# RecoveryBoard.net
KiCad netlist of a schematic drawn in EAGLE
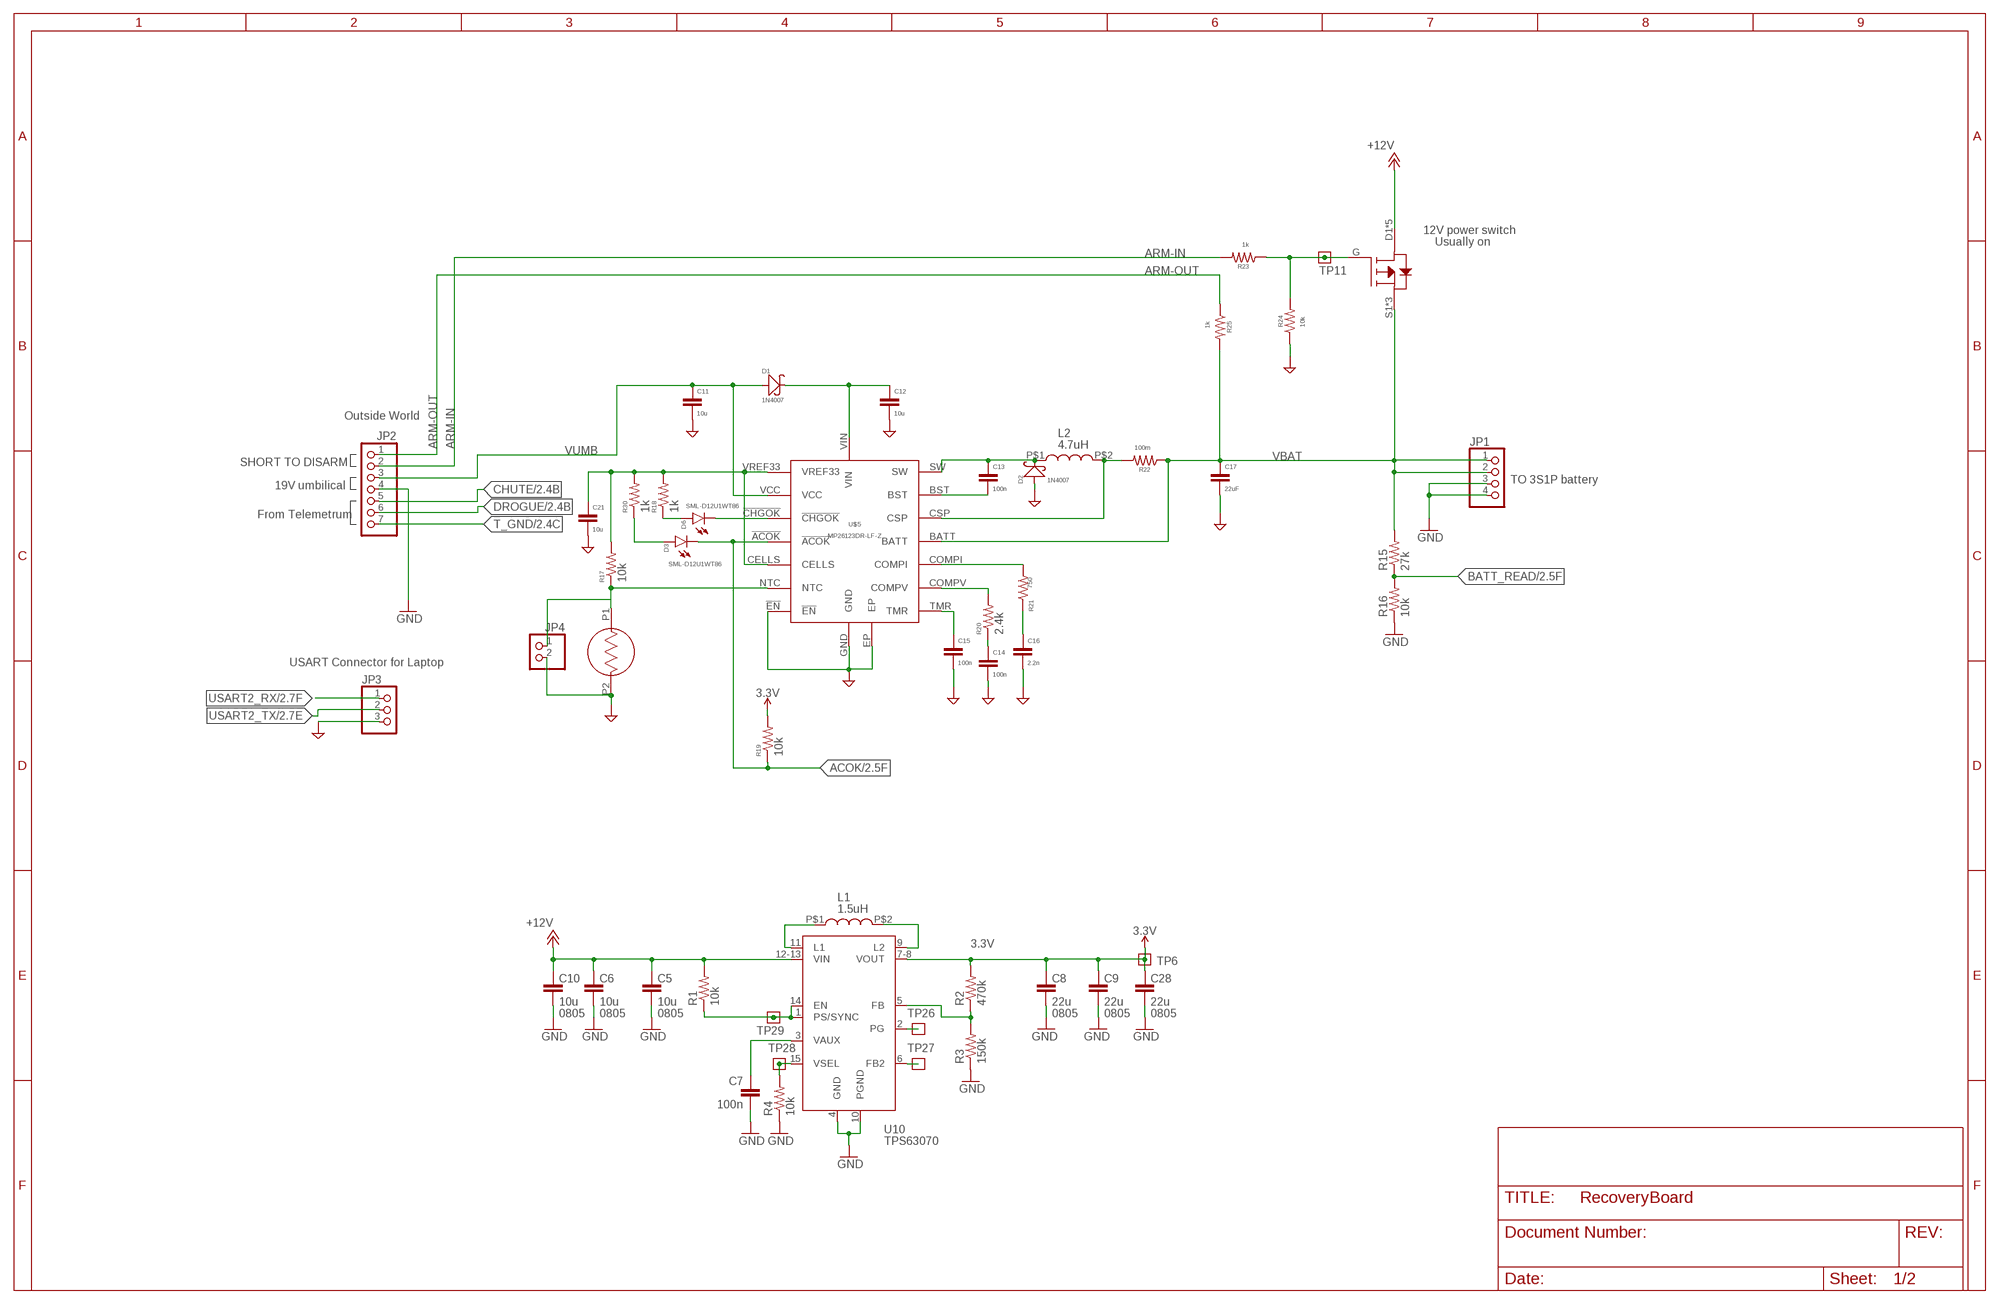
[diagram p0: schematic, sheet 1]
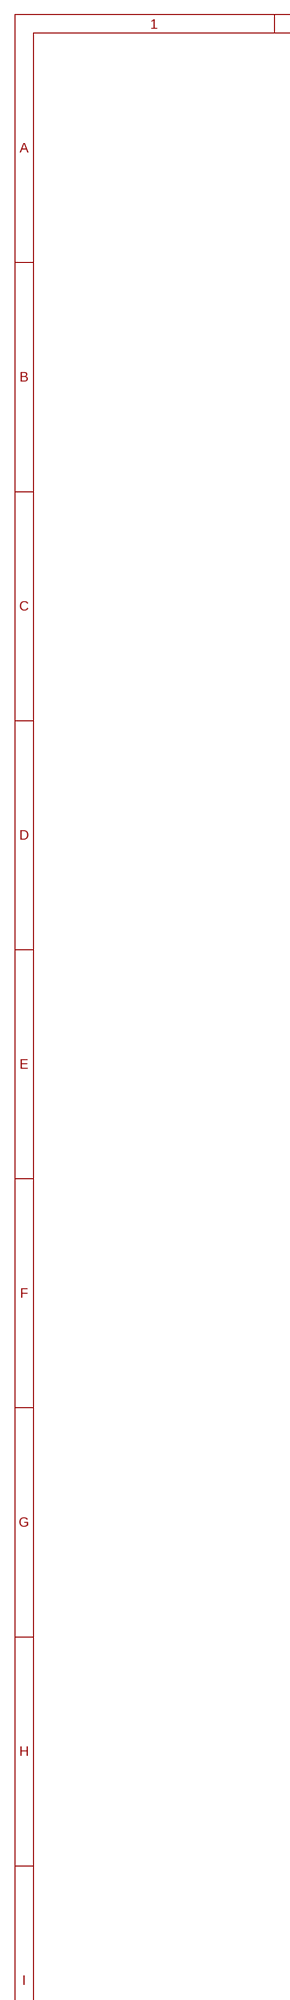
[diagram p1: schematic, sheet 2, part 1 of 2]
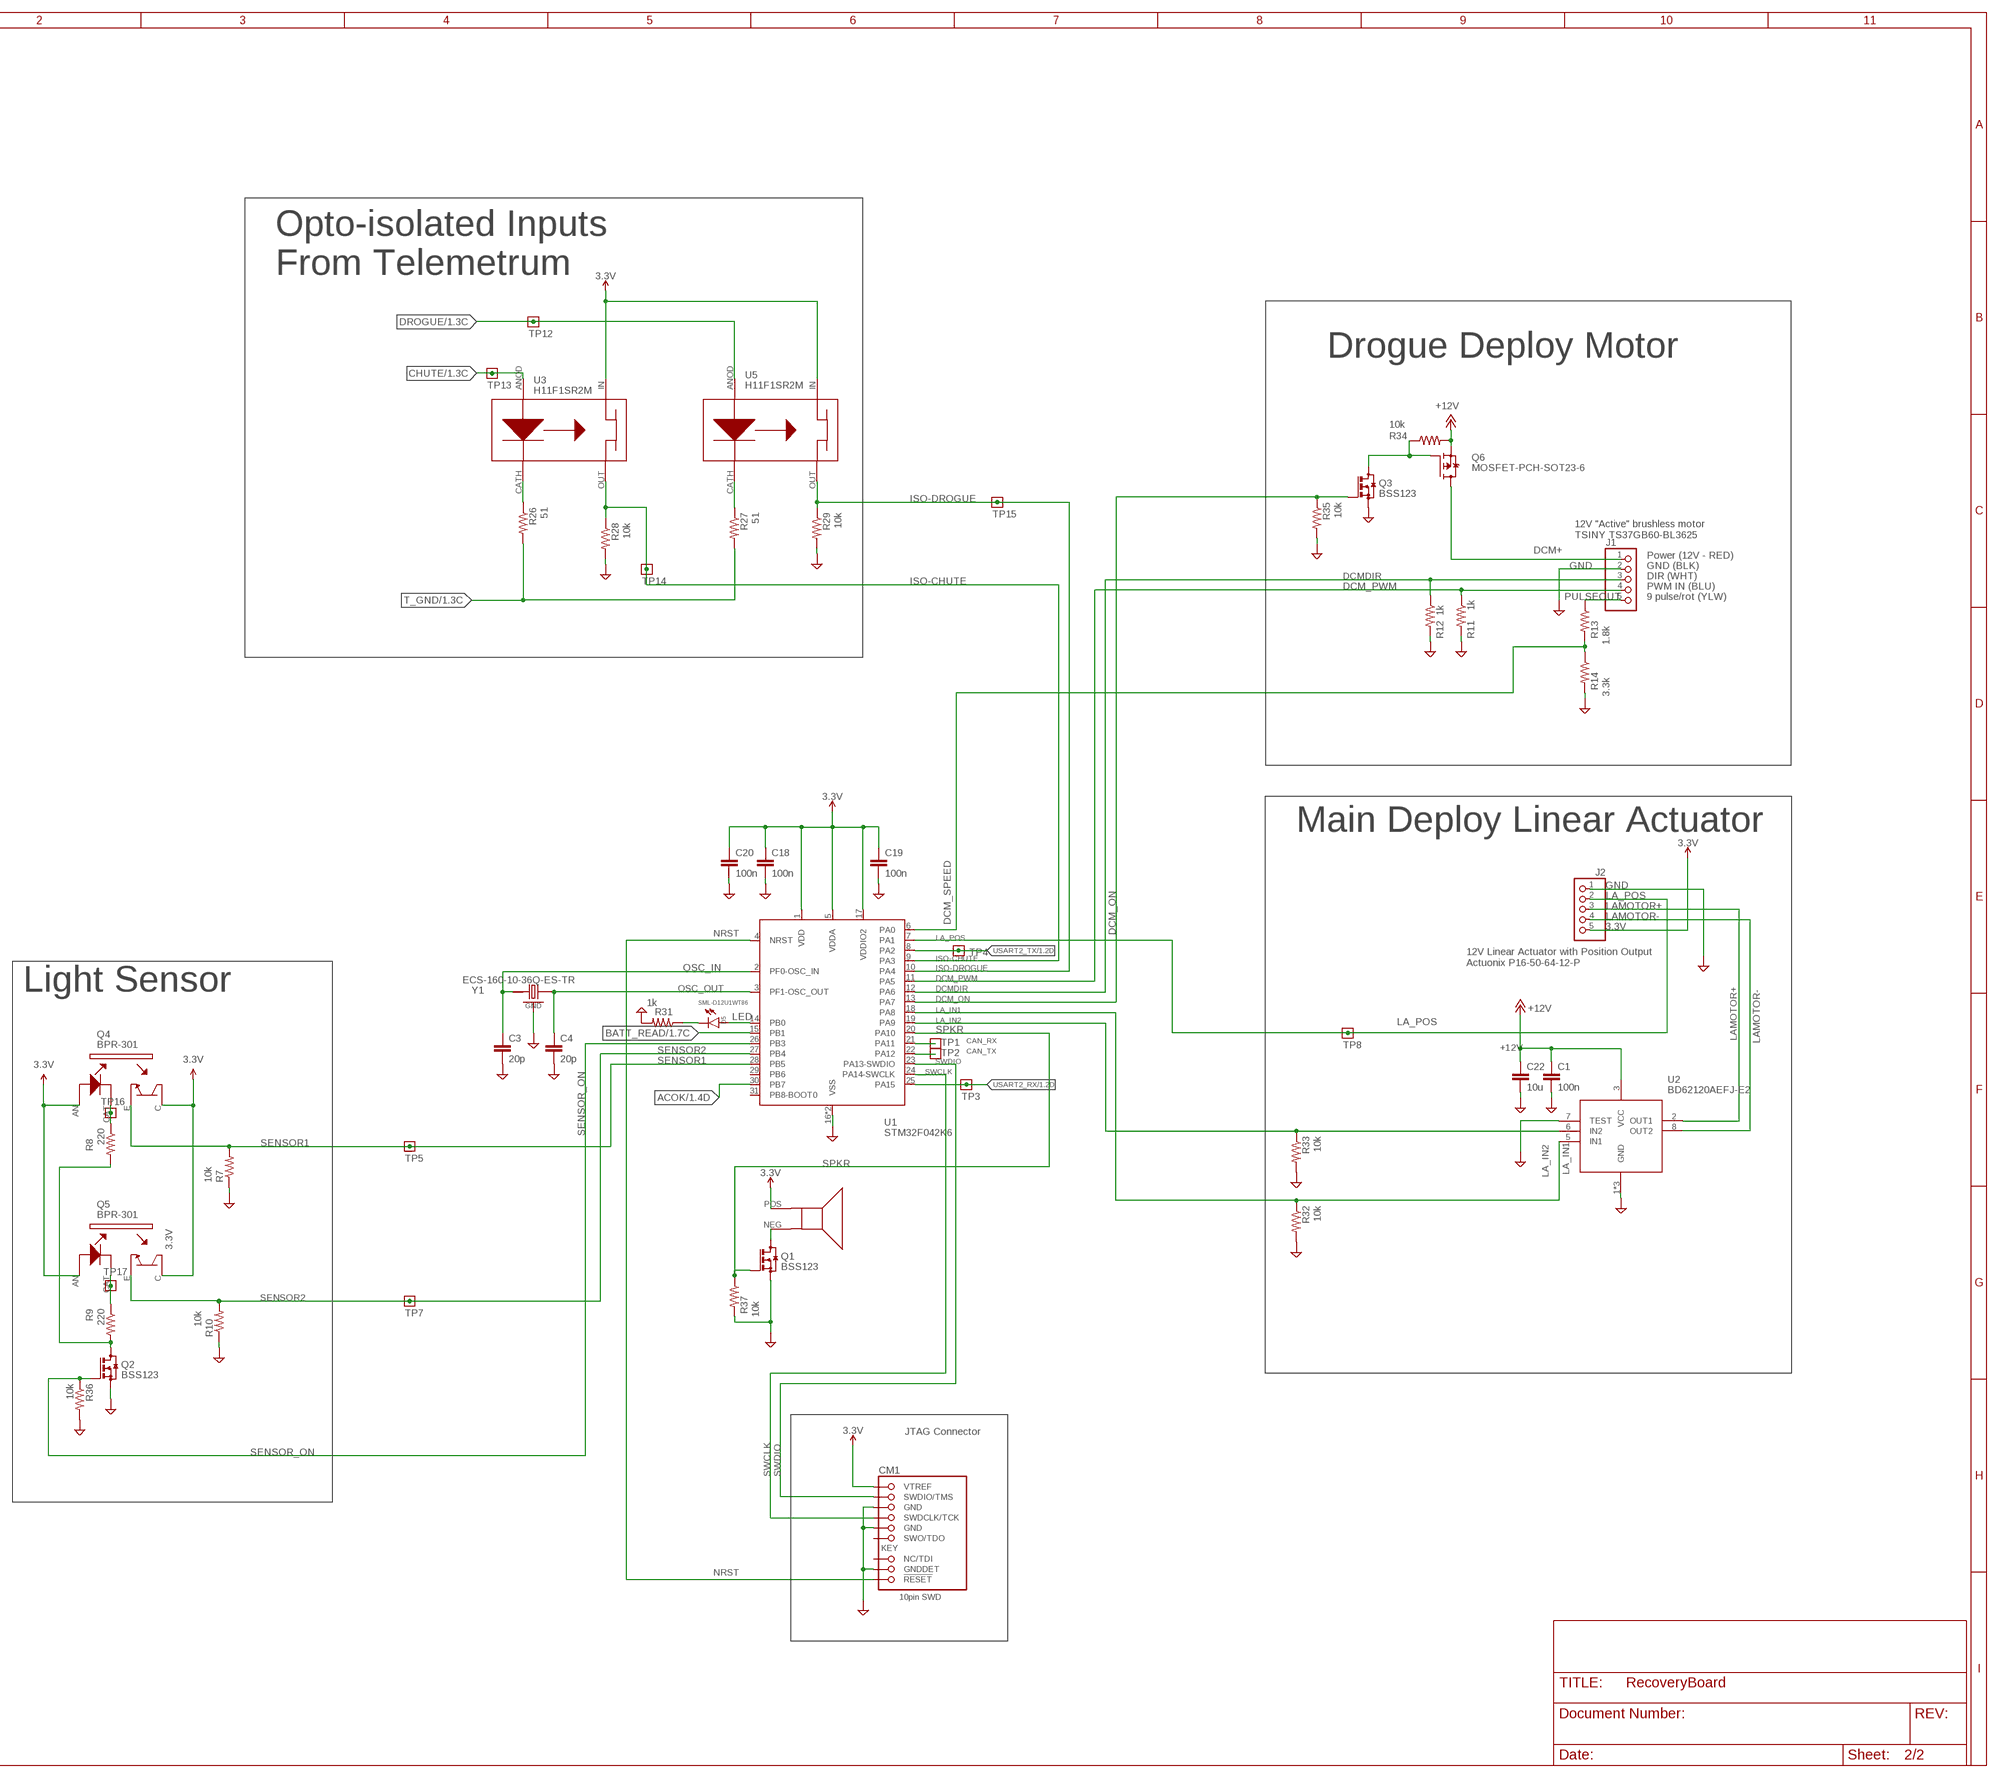
[diagram p2: schematic, sheet 2, part 2 of 2]

(export (version "E")
  (design (tool "Eeschema 10.0.6"))
  (components
    (comp (ref "C5")
      (value "10u")
      (footprint "eagle-import:.0805-C-NOSILK")
      (fields (field (name "MFR") "Samsung") (field (name "MPN") "CL05B104KO5NNNC"))
      (libsource (lib "eagle-import") (part "C-EU0805-C-NOSILK"))
    )
    (comp (ref "C6")
      (value "10u")
      (footprint "eagle-import:.0805-C-NOSILK")
      (libsource (lib "eagle-import") (part "C-EU0805-C-NOSILK"))
    )
    (comp (ref "C7")
      (value "100n")
      (footprint "eagle-import:.0603-C-NOSILK")
      (fields (field (name "MFR") "Samsung") (field (name "MPN") "CL05B104KO5NNNC"))
      (libsource (lib "eagle-import") (part "C-EU0603-C-NOSILK"))
    )
    (comp (ref "C8")
      (value "22u")
      (footprint "eagle-import:.0805-C-NOSILK")
      (fields (field (name "MFR") "Samsung") (field (name "MPN") "CL05B104KO5NNNC"))
      (libsource (lib "eagle-import") (part "C-EU0805-C-NOSILK"))
    )
    (comp (ref "C9")
      (value "22u")
      (footprint "eagle-import:.0805-C-NOSILK")
      (libsource (lib "eagle-import") (part "C-EU0805-C-NOSILK"))
    )
    (comp (ref "C10")
      (value "10u")
      (footprint "eagle-import:.0805-C-NOSILK")
      (libsource (lib "eagle-import") (part "C-EU0805-C-NOSILK"))
    )
    (comp (ref "C11")
      (value "10u")
      (footprint "eagle-import:.0805-C-NOSILK")
      (libsource (lib "eagle-import") (part "C-EU0805-C-NOSILK"))
    )
    (comp (ref "C12")
      (value "10u")
      (footprint "eagle-import:.0805-C-NOSILK")
      (libsource (lib "eagle-import") (part "C-EU0805-C-NOSILK"))
    )
    (comp (ref "C13")
      (value "100n")
      (footprint "eagle-import:.0603-C-NOSILK")
      (libsource (lib "eagle-import") (part "C-EU0603-C-NOSILK"))
    )
    (comp (ref "C14")
      (value "100n")
      (footprint "eagle-import:.0603-C-NOSILK")
      (libsource (lib "eagle-import") (part "C-EU0603-C-NOSILK"))
    )
    (comp (ref "C15")
      (value "100n")
      (footprint "eagle-import:.0603-C-NOSILK")
      (libsource (lib "eagle-import") (part "C-EU0603-C-NOSILK"))
    )
    (comp (ref "C16")
      (value "2.2n")
      (footprint "eagle-import:.0603-C-NOSILK")
      (libsource (lib "eagle-import") (part "C-EU0603-C-NOSILK"))
    )
    (comp (ref "C17")
      (value "22uF")
      (footprint "eagle-import:.0805-C-NOSILK")
      (libsource (lib "eagle-import") (part "C-EU0805-C-NOSILK"))
    )
    (comp (ref "C21")
      (value "10u")
      (footprint "eagle-import:.0805-C-NOSILK")
      (libsource (lib "eagle-import") (part "C-EU0805-C-NOSILK"))
    )
    (comp (ref "C28")
      (value "22u")
      (footprint "eagle-import:.0805-C-NOSILK")
      (libsource (lib "eagle-import") (part "C-EU0805-C-NOSILK"))
    )
    (comp (ref "D1")
      (value "1N4007")
      (footprint "eagle-import:DO-214AC")
      (libsource (lib "eagle-import") (part "DIODE-SCHOTTKY-(DO-214AC)"))
    )
    (comp (ref "D2")
      (value "1N4007")
      (footprint "eagle-import:DO-214AC")
      (libsource (lib "eagle-import") (part "DIODE-SCHOTTKY-(DO-214AC)"))
    )
    (comp (ref "D3")
      (value "SML-D12U1WT86")
      (footprint "eagle-import:CHIPLED_0603")
      (libsource (lib "eagle-import") (part "LEDCHIPLED_0603"))
    )
    (comp (ref "D6")
      (value "SML-D12U1WT86")
      (footprint "eagle-import:CHIPLED_0603")
      (libsource (lib "eagle-import") (part "LEDCHIPLED_0603"))
    )
    (comp (ref "JP1")
      (value "PINHD-1X4")
      (footprint "eagle-import:1X04")
      (libsource (lib "eagle-import") (part "PINHD-1X4"))
    )
    (comp (ref "JP2")
      (value "PINHD-1X7")
      (footprint "eagle-import:1X07")
      (libsource (lib "eagle-import") (part "PINHD-1X7"))
    )
    (comp (ref "JP3")
      (value "PINHD-1X3")
      (footprint "eagle-import:1X03")
      (libsource (lib "eagle-import") (part "PINHD-1X3"))
    )
    (comp (ref "JP4")
      (value "PINHD-1X2")
      (footprint "eagle-import:1X02")
      (libsource (lib "eagle-import") (part "PINHD-1X2"))
    )
    (comp (ref "L1")
      (value "1.5uH")
      (footprint "eagle-import:IHLP2020CZER1R5M11")
      (fields (field (name "MFR") "Vishay Dale") (field (name "MPN") "IHLP2020BZER4R7M11"))
      (libsource (lib "eagle-import") (part "IHLP2020CZER1R5M11"))
    )
    (comp (ref "L2")
      (value "4.7uH")
      (footprint "eagle-import:IHLP2020BZER4R7M11")
      (fields (field (name "MFR") "Vishay Dale") (field (name "MPN") "IHLP2020BZER4R7M11"))
      (libsource (lib "eagle-import") (part "IHLP2020BZER4R7M11"))
    )
    (comp (ref "Q7")
      (value "SI7465DP-T1-E3")
      (footprint "eagle-import:SI7465DP-T1-E3CT-ND")
      (fields (field (name "MFR") "Vishay Siliconix"))
      (libsource (lib "eagle-import") (part "SI7465DP-T1-E3"))
    )
    (comp (ref "R1")
      (value "10k")
      (footprint "eagle-import:.0603-C-NOSILK")
      (fields (field (name "MFR") "Samsung") (field (name "MPN") "RC1005F6653CS"))
      (libsource (lib "eagle-import") (part "R-US_0603-C-NOSILK"))
    )
    (comp (ref "R2")
      (value "470k")
      (footprint "eagle-import:.0603-C-NOSILK")
      (fields (field (name "MFR") "Samsung") (field (name "MPN") "RC1005F6653CS"))
      (libsource (lib "eagle-import") (part "R-US_0603-C-NOSILK"))
    )
    (comp (ref "R3")
      (value "150k")
      (footprint "eagle-import:.0603-C-NOSILK")
      (fields (field (name "MFR") "Samsung") (field (name "MPN") "RC1005F6653CS"))
      (libsource (lib "eagle-import") (part "R-US_0603-C-NOSILK"))
    )
    (comp (ref "R4")
      (value "10k")
      (footprint "eagle-import:.0603-C-NOSILK")
      (fields (field (name "MFR") "Samsung") (field (name "MPN") "RC1005F6653CS"))
      (libsource (lib "eagle-import") (part "R-US_0603-C-NOSILK"))
    )
    (comp (ref "R5")
      (value "NHQ103B375T10")
      (footprint "eagle-import:NHQ103B375T10")
      (libsource (lib "eagle-import") (part "NHQ103B375T10"))
    )
    (comp (ref "R15")
      (value "27k")
      (footprint "eagle-import:.0603-C-NOSILK")
      (fields (field (name "MFR") "Samsung") (field (name "MPN") "RC1005F6653CS"))
      (libsource (lib "eagle-import") (part "R-US_0603-C-NOSILK"))
    )
    (comp (ref "R16")
      (value "10k")
      (footprint "eagle-import:.0603-C-NOSILK")
      (fields (field (name "MFR") "Samsung") (field (name "MPN") "RC1005F6653CS"))
      (libsource (lib "eagle-import") (part "R-US_0603-C-NOSILK"))
    )
    (comp (ref "R17")
      (value "10k")
      (footprint "eagle-import:.0603-C-NOSILK")
      (libsource (lib "eagle-import") (part "R-US_0603-C-NOSILK"))
    )
    (comp (ref "R18")
      (value "1k")
      (footprint "eagle-import:.0603-C-NOSILK")
      (libsource (lib "eagle-import") (part "R-US_0603-C-NOSILK"))
    )
    (comp (ref "R19")
      (value "10k")
      (footprint "eagle-import:.0603-C-NOSILK")
      (libsource (lib "eagle-import") (part "R-US_0603-C-NOSILK"))
    )
    (comp (ref "R20")
      (value "2.4k")
      (footprint "eagle-import:.0603-C-NOSILK")
      (libsource (lib "eagle-import") (part "R-US_0603-C-NOSILK"))
    )
    (comp (ref "R21")
      (value "750")
      (footprint "eagle-import:.0603-C-NOSILK")
      (libsource (lib "eagle-import") (part "R-US_0603-C-NOSILK"))
    )
    (comp (ref "R22")
      (value "100m")
      (footprint "eagle-import:1206-C")
      (libsource (lib "eagle-import") (part "R-US_1206-C"))
    )
    (comp (ref "R23")
      (value "1k")
      (footprint "eagle-import:.0603-C-NOSILK")
      (libsource (lib "eagle-import") (part "R-US_0603-C-NOSILK"))
    )
    (comp (ref "R24")
      (value "10k")
      (footprint "eagle-import:.0603-C-NOSILK")
      (libsource (lib "eagle-import") (part "R-US_0603-C-NOSILK"))
    )
    (comp (ref "R25")
      (value "1k")
      (footprint "eagle-import:.0603-C-NOSILK")
      (libsource (lib "eagle-import") (part "R-US_0603-C-NOSILK"))
    )
    (comp (ref "R30")
      (value "1k")
      (footprint "eagle-import:.0603-C-NOSILK")
      (libsource (lib "eagle-import") (part "R-US_0603-C-NOSILK"))
    )
    (comp (ref "TP6")
      (value "TEST-POINT")
      (footprint "eagle-import:2MM-TEST-POINT")
      (libsource (lib "eagle-import") (part "TEST-POINT"))
    )
    (comp (ref "TP11")
      (value "TEST-POINT")
      (footprint "eagle-import:2MM-TEST-POINT")
      (libsource (lib "eagle-import") (part "TEST-POINT"))
    )
    (comp (ref "TP26")
      (value "TEST-POINT")
      (footprint "eagle-import:2MM-TEST-POINT")
      (libsource (lib "eagle-import") (part "TEST-POINT"))
    )
    (comp (ref "TP27")
      (value "TEST-POINT")
      (footprint "eagle-import:2MM-TEST-POINT")
      (libsource (lib "eagle-import") (part "TEST-POINT"))
    )
    (comp (ref "TP28")
      (value "TEST-POINT")
      (footprint "eagle-import:2MM-TEST-POINT")
      (libsource (lib "eagle-import") (part "TEST-POINT"))
    )
    (comp (ref "TP29")
      (value "TEST-POINT")
      (footprint "eagle-import:2MM-TEST-POINT")
      (libsource (lib "eagle-import") (part "TEST-POINT"))
    )
    (comp (ref "U$5")
      (value "MP26123DR-LF-Z")
      (footprint "eagle-import:MP26123DR-LF-Z")
      (libsource (lib "eagle-import") (part "MP26123DR-LF-Z"))
    )
    (comp (ref "U10")
      (value "TPS63070")
      (footprint "eagle-import:TPS63070X")
      (libsource (lib "eagle-import") (part "TPS63070X"))
    )
    (comp (ref "C1")
      (value "100n")
      (footprint "eagle-import:.0603-C-NOSILK")
      (libsource (lib "eagle-import") (part "C-EU0603-C-NOSILK"))
    )
    (comp (ref "C3")
      (value "20p")
      (footprint "eagle-import:.0603-C-NOSILK")
      (libsource (lib "eagle-import") (part "C-EU0603-C-NOSILK"))
    )
    (comp (ref "C4")
      (value "20p")
      (footprint "eagle-import:.0603-C-NOSILK")
      (libsource (lib "eagle-import") (part "C-EU0603-C-NOSILK"))
    )
    (comp (ref "C18")
      (value "100n")
      (footprint "eagle-import:.0603-C-NOSILK")
      (libsource (lib "eagle-import") (part "C-EU0603-C-NOSILK"))
    )
    (comp (ref "C19")
      (value "100n")
      (footprint "eagle-import:.0603-C-NOSILK")
      (libsource (lib "eagle-import") (part "C-EU0603-C-NOSILK"))
    )
    (comp (ref "C20")
      (value "100n")
      (footprint "eagle-import:.0603-C-NOSILK")
      (libsource (lib "eagle-import") (part "C-EU0603-C-NOSILK"))
    )
    (comp (ref "C22")
      (value "10u")
      (footprint "eagle-import:.0805-A-NOSILK")
      (libsource (lib "eagle-import") (part "C-EU0805-A-NOSILK"))
    )
    (comp (ref "CM1")
      (value "FTSH-105-XX-X-DV-K")
      (footprint "eagle-import:CON10_2X5_DUK_FTSH")
      (libsource (lib "eagle-import") (part "FTSH-105-XX-X-DV-K"))
    )
    (comp (ref "D5")
      (value "SML-D12U1WT86")
      (footprint "eagle-import:CHIPLED_0603")
      (libsource (lib "eagle-import") (part "LEDCHIPLED_0603"))
    )
    (comp (ref "J1")
      (value "PINHD-1X5")
      (footprint "eagle-import:1X05")
      (libsource (lib "eagle-import") (part "PINHD-1X5"))
    )
    (comp (ref "J2")
      (value "PINHD-1X5")
      (footprint "eagle-import:1X05")
      (libsource (lib "eagle-import") (part "PINHD-1X5"))
    )
    (comp (ref "Q1")
      (value "BSS123")
      (footprint "eagle-import:SOT23")
      (libsource (lib "eagle-import") (part "BSS123"))
    )
    (comp (ref "Q2")
      (value "BSS123")
      (footprint "eagle-import:SOT23")
      (libsource (lib "eagle-import") (part "BSS123"))
    )
    (comp (ref "Q3")
      (value "BSS123")
      (footprint "eagle-import:SOT23")
      (libsource (lib "eagle-import") (part "BSS123"))
    )
    (comp (ref "Q4")
      (value "BPR-301")
      (footprint "eagle-import:BPR-301")
      (libsource (lib "eagle-import") (part "BPR-301"))
    )
    (comp (ref "Q5")
      (value "BPR-301")
      (footprint "eagle-import:BPR-301")
      (libsource (lib "eagle-import") (part "BPR-301"))
    )
    (comp (ref "Q6")
      (value "MOSFET-PCH-SOT23-6")
      (footprint "eagle-import:SOT23-6")
      (libsource (lib "eagle-import") (part "MOSFET-PCH-SOT23-6"))
    )
    (comp (ref "R7")
      (value "10k")
      (footprint "eagle-import:.0603-C-NOSILK")
      (libsource (lib "eagle-import") (part "R-US_0603-C-NOSILK"))
    )
    (comp (ref "R8")
      (value "220")
      (footprint "eagle-import:.0603-C-NOSILK")
      (libsource (lib "eagle-import") (part "R-US_0603-C-NOSILK"))
    )
    (comp (ref "R9")
      (value "220")
      (footprint "eagle-import:.0603-C-NOSILK")
      (libsource (lib "eagle-import") (part "R-US_0603-C-NOSILK"))
    )
    (comp (ref "R10")
      (value "10k")
      (footprint "eagle-import:.0603-C-NOSILK")
      (libsource (lib "eagle-import") (part "R-US_0603-C-NOSILK"))
    )
    (comp (ref "R11")
      (value "1k")
      (footprint "eagle-import:.0603-C-NOSILK")
      (libsource (lib "eagle-import") (part "R-US_0603-C-NOSILK"))
    )
    (comp (ref "R12")
      (value "1k")
      (footprint "eagle-import:.0603-C-NOSILK")
      (libsource (lib "eagle-import") (part "R-US_0603-C-NOSILK"))
    )
    (comp (ref "R13")
      (value "1.8k")
      (footprint "eagle-import:.0603-C-NOSILK")
      (libsource (lib "eagle-import") (part "R-US_0603-C-NOSILK"))
    )
    (comp (ref "R14")
      (value "3.3k")
      (footprint "eagle-import:.0603-C-NOSILK")
      (libsource (lib "eagle-import") (part "R-US_0603-C-NOSILK"))
    )
    (comp (ref "R26")
      (value "51")
      (footprint "eagle-import:.0603-C-NOSILK")
      (libsource (lib "eagle-import") (part "R-US_0603-C-NOSILK"))
    )
    (comp (ref "R27")
      (value "51")
      (footprint "eagle-import:.0603-C-NOSILK")
      (libsource (lib "eagle-import") (part "R-US_0603-C-NOSILK"))
    )
    (comp (ref "R28")
      (value "10k")
      (footprint "eagle-import:.0603-C-NOSILK")
      (libsource (lib "eagle-import") (part "R-US_0603-C-NOSILK"))
    )
    (comp (ref "R29")
      (value "10k")
      (footprint "eagle-import:.0603-C-NOSILK")
      (libsource (lib "eagle-import") (part "R-US_0603-C-NOSILK"))
    )
    (comp (ref "R31")
      (value "1k")
      (footprint "eagle-import:.0603-C-NOSILK")
      (libsource (lib "eagle-import") (part "R-US_0603-C-NOSILK"))
    )
    (comp (ref "R32")
      (value "10k")
      (footprint "eagle-import:.0603-C-NOSILK")
      (libsource (lib "eagle-import") (part "R-US_0603-C-NOSILK"))
    )
    (comp (ref "R33")
      (value "10k")
      (footprint "eagle-import:.0603-C-NOSILK")
      (libsource (lib "eagle-import") (part "R-US_0603-C-NOSILK"))
    )
    (comp (ref "R34")
      (value "10k")
      (footprint "eagle-import:.0603-C-NOSILK")
      (libsource (lib "eagle-import") (part "R-US_0603-C-NOSILK"))
    )
    (comp (ref "R35")
      (value "10k")
      (footprint "eagle-import:.0603-C-NOSILK")
      (libsource (lib "eagle-import") (part "R-US_0603-C-NOSILK"))
    )
    (comp (ref "R36")
      (value "10k")
      (footprint "eagle-import:.0603-C-NOSILK")
      (libsource (lib "eagle-import") (part "R-US_0603-C-NOSILK"))
    )
    (comp (ref "R37")
      (value "10k")
      (footprint "eagle-import:.0603-C-NOSILK")
      (libsource (lib "eagle-import") (part "R-US_0603-C-NOSILK"))
    )
    (comp (ref "TP1")
      (value "TEST-POINT")
      (footprint "eagle-import:2MM-TEST-POINT")
      (libsource (lib "eagle-import") (part "TEST-POINT"))
    )
    (comp (ref "TP2")
      (value "TEST-POINT")
      (footprint "eagle-import:2MM-TEST-POINT")
      (libsource (lib "eagle-import") (part "TEST-POINT"))
    )
    (comp (ref "TP3")
      (value "TEST-POINT")
      (footprint "eagle-import:2MM-TEST-POINT")
      (libsource (lib "eagle-import") (part "TEST-POINT"))
    )
    (comp (ref "TP4")
      (value "TEST-POINT")
      (footprint "eagle-import:2MM-TEST-POINT")
      (libsource (lib "eagle-import") (part "TEST-POINT"))
    )
    (comp (ref "TP5")
      (value "TEST-POINT")
      (footprint "eagle-import:2MM-TEST-POINT")
      (libsource (lib "eagle-import") (part "TEST-POINT"))
    )
    (comp (ref "TP7")
      (value "TEST-POINT")
      (footprint "eagle-import:2MM-TEST-POINT")
      (libsource (lib "eagle-import") (part "TEST-POINT"))
    )
    (comp (ref "TP8")
      (value "TEST-POINT")
      (footprint "eagle-import:2MM-TEST-POINT")
      (libsource (lib "eagle-import") (part "TEST-POINT"))
    )
    (comp (ref "TP12")
      (value "TEST-POINT")
      (footprint "eagle-import:2MM-TEST-POINT")
      (libsource (lib "eagle-import") (part "TEST-POINT"))
    )
    (comp (ref "TP13")
      (value "TEST-POINT")
      (footprint "eagle-import:2MM-TEST-POINT")
      (libsource (lib "eagle-import") (part "TEST-POINT"))
    )
    (comp (ref "TP14")
      (value "TEST-POINT")
      (footprint "eagle-import:2MM-TEST-POINT")
      (libsource (lib "eagle-import") (part "TEST-POINT"))
    )
    (comp (ref "TP15")
      (value "TEST-POINT")
      (footprint "eagle-import:2MM-TEST-POINT")
      (libsource (lib "eagle-import") (part "TEST-POINT"))
    )
    (comp (ref "TP16")
      (value "TEST-POINT")
      (footprint "eagle-import:2MM-TEST-POINT")
      (libsource (lib "eagle-import") (part "TEST-POINT"))
    )
    (comp (ref "TP17")
      (value "TEST-POINT")
      (footprint "eagle-import:2MM-TEST-POINT")
      (libsource (lib "eagle-import") (part "TEST-POINT"))
    )
    (comp (ref "U$7")
      (value "SMT-0440-S-R")
      (footprint "eagle-import:SMT-0440-S-R")
      (libsource (lib "eagle-import") (part "SMT-0440-S-R"))
    )
    (comp (ref "U1")
      (value "STM32F042K6")
      (footprint "eagle-import:QFP32-7X7")
      (libsource (lib "eagle-import") (part "STM32F042K6"))
    )
    (comp (ref "U2")
      (value "BD62120AEFJ-E2")
      (footprint "eagle-import:SOIC127P600X100-9N")
      (fields (field (name "MOUSER_PART_NUMBER") "755-BD62120AEFJ-E2"))
      (libsource (lib "eagle-import") (part "BD62120AEFJ-E2"))
    )
    (comp (ref "U3")
      (value "H11F1SR2M")
      (footprint "eagle-import:H11F1SR2M")
      (libsource (lib "eagle-import") (part "H11F1SR2M"))
    )
    (comp (ref "U5")
      (value "H11F1SR2M")
      (footprint "eagle-import:H11F1SR2M")
      (libsource (lib "eagle-import") (part "H11F1SR2M"))
    )
    (comp (ref "Y1")
      (value "ECS-160-10-36Q-ES-TR")
      (footprint "eagle-import:XTAL_ECS-160-10-36Q-ES-TR")
      (fields (field (name "DIGI-KEY_PART_NUMBER") "XC2181CT-ND") (field (name "MF") "ECS Inc."))
      (libsource (lib "eagle-import") (part "ECS-160-10-36Q-ES-TR"))
    )
  )
  (nets
    (net (code "1") (name "+12V") (class "Default")
      (node (ref "C1") (pin "1") (pinfunction "1_1") (pintype "passive"))
      (node (ref "C10") (pin "1") (pinfunction "1_1") (pintype "passive"))
      (node (ref "C22") (pin "1") (pinfunction "1_1") (pintype "passive"))
      (node (ref "C5") (pin "1") (pinfunction "1_1") (pintype "passive"))
      (node (ref "C6") (pin "1") (pinfunction "1_1") (pintype "passive"))
      (node (ref "Q6") (pin "4") (pinfunction "S_4") (pintype "passive"))
      (node (ref "Q7") (pin "D1") (pinfunction "D_D1") (pintype "bidirectional"))
      (node (ref "Q7") (pin "D2") (pinfunction "D_D2") (pintype "bidirectional"))
      (node (ref "Q7") (pin "D3") (pinfunction "D_D3") (pintype "bidirectional"))
      (node (ref "Q7") (pin "D4") (pinfunction "D_D4") (pintype "bidirectional"))
      (node (ref "Q7") (pin "DPAD") (pinfunction "D_DPAD") (pintype "bidirectional"))
      (node (ref "R1") (pin "2") (pinfunction "2_2") (pintype "passive"))
      (node (ref "R34") (pin "2") (pinfunction "2_2") (pintype "passive"))
      (node (ref "U10") (pin "12-13") (pinfunction "VIN_12-13") (pintype "power_in"))
      (node (ref "U2") (pin "3") (pinfunction "VCC_3") (pintype "bidirectional"))
    )
    (net (code "2") (name "3.3V") (class "Default")
      (node (ref "C18") (pin "1") (pinfunction "1_1") (pintype "passive"))
      (node (ref "C19") (pin "1") (pinfunction "1_1") (pintype "passive"))
      (node (ref "C20") (pin "1") (pinfunction "1_1") (pintype "passive"))
      (node (ref "C28") (pin "1") (pinfunction "1_1") (pintype "passive"))
      (node (ref "C8") (pin "1") (pinfunction "1_1") (pintype "passive"))
      (node (ref "C9") (pin "1") (pinfunction "1_1") (pintype "passive"))
      (node (ref "CM1") (pin "1") (pinfunction "VTREF_1") (pintype "passive"))
      (node (ref "J2") (pin "5") (pinfunction "5_5") (pintype "passive"))
      (node (ref "Q4") (pin "AN") (pinfunction "ANOD_AN") (pintype "bidirectional"))
      (node (ref "Q4") (pin "C") (pinfunction "COLL_C") (pintype "bidirectional"))
      (node (ref "Q5") (pin "AN") (pinfunction "ANOD_AN") (pintype "bidirectional"))
      (node (ref "Q5") (pin "C") (pinfunction "COLL_C") (pintype "bidirectional"))
      (node (ref "R19") (pin "2") (pinfunction "2_2") (pintype "passive"))
      (node (ref "R2") (pin "2") (pinfunction "2_2") (pintype "passive"))
      (node (ref "TP6") (pin "1") (pinfunction "1_1") (pintype "passive"))
      (node (ref "U$7") (pin "POS") (pinfunction "POS_POS") (pintype "bidirectional"))
      (node (ref "U1") (pin "1") (pinfunction "VDD_1") (pintype "power_in"))
      (node (ref "U1") (pin "17") (pinfunction "VDDIO2_17") (pintype "power_in"))
      (node (ref "U1") (pin "5") (pinfunction "VDDA_5") (pintype "power_in"))
      (node (ref "U10") (pin "7-8") (pinfunction "VOUT_7-8") (pintype "power_in"))
      (node (ref "U3") (pin "IN") (pinfunction "IN_IN") (pintype "bidirectional"))
      (node (ref "U5") (pin "IN") (pinfunction "IN_IN") (pintype "bidirectional"))
    )
    (net (code "3") (name "ACOK") (class "Default")
      (node (ref "D3") (pin "C") (pinfunction "C_C") (pintype "passive"))
      (node (ref "R19") (pin "1") (pinfunction "1_1") (pintype "passive"))
      (node (ref "U$5") (pin "!ACOK") (pinfunction "~{ACOK}_!ACOK") (pintype "bidirectional"))
      (node (ref "U1") (pin "30") (pinfunction "PB7_30") (pintype "bidirectional"))
    )
    (net (code "4") (name "ARM-IN") (class "Default")
      (node (ref "JP2") (pin "2") (pinfunction "2_2") (pintype "passive"))
      (node (ref "R23") (pin "2") (pinfunction "2_2") (pintype "passive"))
    )
    (net (code "5") (name "ARM-OUT") (class "Default")
      (node (ref "JP2") (pin "1") (pinfunction "1_1") (pintype "passive"))
      (node (ref "R25") (pin "1") (pinfunction "1_1") (pintype "passive"))
    )
    (net (code "6") (name "BATT_READ") (class "Default")
      (node (ref "R15") (pin "1") (pinfunction "1_1") (pintype "passive"))
      (node (ref "R16") (pin "2") (pinfunction "2_2") (pintype "passive"))
      (node (ref "U1") (pin "15") (pinfunction "PB1_15") (pintype "bidirectional"))
    )
    (net (code "7") (name "CAN_RX") (class "Default")
      (node (ref "TP1") (pin "1") (pinfunction "1_1") (pintype "passive"))
      (node (ref "U1") (pin "21") (pinfunction "PA11_21") (pintype "bidirectional"))
    )
    (net (code "8") (name "CAN_TX") (class "Default")
      (node (ref "TP2") (pin "1") (pinfunction "1_1") (pintype "passive"))
      (node (ref "U1") (pin "22") (pinfunction "PA12_22") (pintype "bidirectional"))
    )
    (net (code "9") (name "CHUTE") (class "Default")
      (node (ref "JP2") (pin "5") (pinfunction "5_5") (pintype "passive"))
      (node (ref "TP13") (pin "1") (pinfunction "1_1") (pintype "passive"))
      (node (ref "U3") (pin "ANOD") (pinfunction "ANOD_ANOD") (pintype "bidirectional"))
    )
    (net (code "10") (name "DCM+") (class "Default")
      (node (ref "J1") (pin "1") (pinfunction "1_1") (pintype "passive"))
      (node (ref "Q6") (pin "1") (pinfunction "D_1") (pintype "passive"))
      (node (ref "Q6") (pin "2") (pinfunction "D_2") (pintype "passive"))
      (node (ref "Q6") (pin "5") (pinfunction "D_5") (pintype "passive"))
      (node (ref "Q6") (pin "6") (pinfunction "D_6") (pintype "passive"))
    )
    (net (code "11") (name "DCMDIR") (class "Default")
      (node (ref "J1") (pin "3") (pinfunction "3_3") (pintype "passive"))
      (node (ref "R12") (pin "1") (pinfunction "1_1") (pintype "passive"))
      (node (ref "U1") (pin "12") (pinfunction "PA6_12") (pintype "bidirectional"))
    )
    (net (code "12") (name "DCM_ON") (class "Default")
      (node (ref "Q3") (pin "1") (pinfunction "G_1") (pintype "passive"))
      (node (ref "R35") (pin "1") (pinfunction "1_1") (pintype "passive"))
      (node (ref "U1") (pin "13") (pinfunction "PA7_13") (pintype "bidirectional"))
    )
    (net (code "13") (name "DCM_PWM") (class "Default")
      (node (ref "J1") (pin "4") (pinfunction "4_4") (pintype "passive"))
      (node (ref "R11") (pin "1") (pinfunction "1_1") (pintype "passive"))
      (node (ref "U1") (pin "11") (pinfunction "PA5_11") (pintype "bidirectional"))
    )
    (net (code "14") (name "DCM_SPEED") (class "Default")
      (node (ref "R13") (pin "2") (pinfunction "2_2") (pintype "passive"))
      (node (ref "R14") (pin "1") (pinfunction "1_1") (pintype "passive"))
      (node (ref "U1") (pin "6") (pinfunction "PA0_6") (pintype "bidirectional"))
    )
    (net (code "15") (name "DROGUE") (class "Default")
      (node (ref "JP2") (pin "6") (pinfunction "6_6") (pintype "passive"))
      (node (ref "TP12") (pin "1") (pinfunction "1_1") (pintype "passive"))
      (node (ref "U5") (pin "ANOD") (pinfunction "ANOD_ANOD") (pintype "bidirectional"))
    )
    (net (code "16") (name "GND") (class "Default")
      (node (ref "C1") (pin "2") (pinfunction "2_2") (pintype "passive"))
      (node (ref "C10") (pin "2") (pinfunction "2_2") (pintype "passive"))
      (node (ref "C11") (pin "2") (pinfunction "2_2") (pintype "passive"))
      (node (ref "C12") (pin "2") (pinfunction "2_2") (pintype "passive"))
      (node (ref "C14") (pin "2") (pinfunction "2_2") (pintype "passive"))
      (node (ref "C15") (pin "2") (pinfunction "2_2") (pintype "passive"))
      (node (ref "C16") (pin "2") (pinfunction "2_2") (pintype "passive"))
      (node (ref "C17") (pin "2") (pinfunction "2_2") (pintype "passive"))
      (node (ref "C18") (pin "2") (pinfunction "2_2") (pintype "passive"))
      (node (ref "C19") (pin "2") (pinfunction "2_2") (pintype "passive"))
      (node (ref "C20") (pin "2") (pinfunction "2_2") (pintype "passive"))
      (node (ref "C21") (pin "2") (pinfunction "2_2") (pintype "passive"))
      (node (ref "C22") (pin "2") (pinfunction "2_2") (pintype "passive"))
      (node (ref "C28") (pin "2") (pinfunction "2_2") (pintype "passive"))
      (node (ref "C3") (pin "2") (pinfunction "2_2") (pintype "passive"))
      (node (ref "C4") (pin "2") (pinfunction "2_2") (pintype "passive"))
      (node (ref "C5") (pin "2") (pinfunction "2_2") (pintype "passive"))
      (node (ref "C6") (pin "2") (pinfunction "2_2") (pintype "passive"))
      (node (ref "C7") (pin "2") (pinfunction "2_2") (pintype "passive"))
      (node (ref "C8") (pin "2") (pinfunction "2_2") (pintype "passive"))
      (node (ref "C9") (pin "2") (pinfunction "2_2") (pintype "passive"))
      (node (ref "CM1") (pin "3") (pinfunction "GND_3") (pintype "passive"))
      (node (ref "CM1") (pin "5") (pinfunction "GND_5") (pintype "passive"))
      (node (ref "CM1") (pin "9") (pinfunction "GNDDET_9") (pintype "passive"))
      (node (ref "D2") (pin "1") (pinfunction "+_1") (pintype "passive"))
      (node (ref "J1") (pin "2") (pinfunction "2_2") (pintype "passive"))
      (node (ref "J2") (pin "1") (pinfunction "1_1") (pintype "passive"))
      (node (ref "JP1") (pin "3") (pinfunction "3_3") (pintype "passive"))
      (node (ref "JP1") (pin "4") (pinfunction "4_4") (pintype "passive"))
      (node (ref "JP2") (pin "4") (pinfunction "4_4") (pintype "passive"))
      (node (ref "JP3") (pin "3") (pinfunction "3_3") (pintype "passive"))
      (node (ref "JP4") (pin "2") (pinfunction "2_2") (pintype "passive"))
      (node (ref "Q1") (pin "2") (pinfunction "S_2") (pintype "passive"))
      (node (ref "Q2") (pin "2") (pinfunction "S_2") (pintype "passive"))
      (node (ref "Q3") (pin "2") (pinfunction "S_2") (pintype "passive"))
      (node (ref "R10") (pin "1") (pinfunction "1_1") (pintype "passive"))
      (node (ref "R11") (pin "2") (pinfunction "2_2") (pintype "passive"))
      (node (ref "R12") (pin "2") (pinfunction "2_2") (pintype "passive"))
      (node (ref "R14") (pin "2") (pinfunction "2_2") (pintype "passive"))
      (node (ref "R16") (pin "1") (pinfunction "1_1") (pintype "passive"))
      (node (ref "R24") (pin "1") (pinfunction "1_1") (pintype "passive"))
      (node (ref "R28") (pin "2") (pinfunction "2_2") (pintype "passive"))
      (node (ref "R29") (pin "2") (pinfunction "2_2") (pintype "passive"))
      (node (ref "R3") (pin "1") (pinfunction "1_1") (pintype "passive"))
      (node (ref "R31") (pin "2") (pinfunction "2_2") (pintype "passive"))
      (node (ref "R32") (pin "2") (pinfunction "2_2") (pintype "passive"))
      (node (ref "R33") (pin "2") (pinfunction "2_2") (pintype "passive"))
      (node (ref "R35") (pin "2") (pinfunction "2_2") (pintype "passive"))
      (node (ref "R36") (pin "2") (pinfunction "2_2") (pintype "passive"))
      (node (ref "R37") (pin "2") (pinfunction "2_2") (pintype "passive"))
      (node (ref "R4") (pin "1") (pinfunction "1_1") (pintype "passive"))
      (node (ref "R5") (pin "P2") (pinfunction "P$2_P2") (pintype "bidirectional"))
      (node (ref "R7") (pin "1") (pinfunction "1_1") (pintype "passive"))
      (node (ref "U$5") (pin "!EN") (pinfunction "~{EN}_!EN") (pintype "bidirectional"))
      (node (ref "U$5") (pin "EP") (pinfunction "EP_EP") (pintype "bidirectional"))
      (node (ref "U$5") (pin "GND") (pinfunction "GND_GND") (pintype "bidirectional"))
      (node (ref "U1") (pin "16") (pinfunction "VSS_16") (pintype "power_in"))
      (node (ref "U1") (pin "32") (pinfunction "VSS_32") (pintype "power_in"))
      (node (ref "U10") (pin "10") (pinfunction "PGND_10") (pintype "power_in"))
      (node (ref "U10") (pin "4") (pinfunction "GND_4") (pintype "power_in"))
      (node (ref "U2") (pin "1") (pinfunction "GND_1") (pintype "bidirectional"))
      (node (ref "U2") (pin "4") (pinfunction "GND_4") (pintype "bidirectional"))
      (node (ref "U2") (pin "7") (pinfunction "TEST_7") (pintype "bidirectional"))
      (node (ref "U2") (pin "9") (pinfunction "GND_9") (pintype "bidirectional"))
      (node (ref "Y1") (pin "GND") (pinfunction "GND_GND") (pintype "power_in"))
      (node (ref "Y1") (pin "GND2") (pinfunction "GND_GND2") (pintype "power_in"))
    )
    (net (code "17") (name "ISO-CHUTE") (class "Default")
      (node (ref "R28") (pin "1") (pinfunction "1_1") (pintype "passive"))
      (node (ref "TP14") (pin "1") (pinfunction "1_1") (pintype "passive"))
      (node (ref "U1") (pin "9") (pinfunction "PA3_9") (pintype "bidirectional"))
      (node (ref "U3") (pin "OUT") (pinfunction "OUT_OUT") (pintype "bidirectional"))
    )
    (net (code "18") (name "ISO-DROGUE") (class "Default")
      (node (ref "R29") (pin "1") (pinfunction "1_1") (pintype "passive"))
      (node (ref "TP15") (pin "1") (pinfunction "1_1") (pintype "passive"))
      (node (ref "U1") (pin "10") (pinfunction "PA4_10") (pintype "bidirectional"))
      (node (ref "U5") (pin "OUT") (pinfunction "OUT_OUT") (pintype "bidirectional"))
    )
    (net (code "19") (name "LAMOTOR+") (class "Default")
      (node (ref "J2") (pin "3") (pinfunction "3_3") (pintype "passive"))
      (node (ref "U2") (pin "2") (pinfunction "OUT1_2") (pintype "bidirectional"))
    )
    (net (code "20") (name "LAMOTOR-") (class "Default")
      (node (ref "J2") (pin "4") (pinfunction "4_4") (pintype "passive"))
      (node (ref "U2") (pin "8") (pinfunction "OUT2_8") (pintype "bidirectional"))
    )
    (net (code "21") (name "LA_IN1") (class "Default")
      (node (ref "R32") (pin "1") (pinfunction "1_1") (pintype "passive"))
      (node (ref "U1") (pin "18") (pinfunction "PA8_18") (pintype "bidirectional"))
      (node (ref "U2") (pin "5") (pinfunction "IN1_5") (pintype "bidirectional"))
    )
    (net (code "22") (name "LA_IN2") (class "Default")
      (node (ref "R33") (pin "1") (pinfunction "1_1") (pintype "passive"))
      (node (ref "U1") (pin "19") (pinfunction "PA9_19") (pintype "bidirectional"))
      (node (ref "U2") (pin "6") (pinfunction "IN2_6") (pintype "bidirectional"))
    )
    (net (code "23") (name "LA_POS") (class "Default")
      (node (ref "J2") (pin "2") (pinfunction "2_2") (pintype "passive"))
      (node (ref "TP8") (pin "1") (pinfunction "1_1") (pintype "passive"))
      (node (ref "U1") (pin "7") (pinfunction "PA1_7") (pintype "bidirectional"))
    )
    (net (code "24") (name "LED") (class "Default")
      (node (ref "D5") (pin "A") (pinfunction "A_A") (pintype "passive"))
      (node (ref "U1") (pin "14") (pinfunction "PB0_14") (pintype "bidirectional"))
    )
    (net (code "25") (name "NRST") (class "Default")
      (node (ref "CM1") (pin "10") (pinfunction "~{RESET}_10") (pintype "passive"))
      (node (ref "U1") (pin "4") (pinfunction "NRST_4") (pintype "bidirectional"))
    )
    (net (code "26") (name "Net-(C13-Pad2)") (class "Default")
      (node (ref "C13") (pin "2") (pinfunction "2_2") (pintype "passive"))
      (node (ref "U$5") (pin "BST") (pinfunction "BST_BST") (pintype "bidirectional"))
    )
    (net (code "27") (name "Net-(C14-Pad1)") (class "Default")
      (node (ref "C14") (pin "1") (pinfunction "1_1") (pintype "passive"))
      (node (ref "R20") (pin "1") (pinfunction "1_1") (pintype "passive"))
    )
    (net (code "28") (name "Net-(C15-Pad1)") (class "Default")
      (node (ref "C15") (pin "1") (pinfunction "1_1") (pintype "passive"))
      (node (ref "U$5") (pin "TMR") (pinfunction "TMR_TMR") (pintype "bidirectional"))
    )
    (net (code "29") (name "Net-(C16-Pad1)") (class "Default")
      (node (ref "C16") (pin "1") (pinfunction "1_1") (pintype "passive"))
      (node (ref "R21") (pin "1") (pinfunction "1_1") (pintype "passive"))
    )
    (net (code "30") (name "Net-(C21-Pad1)") (class "Default")
      (node (ref "C21") (pin "1") (pinfunction "1_1") (pintype "passive"))
      (node (ref "R17") (pin "2") (pinfunction "2_2") (pintype "passive"))
      (node (ref "R18") (pin "2") (pinfunction "2_2") (pintype "passive"))
      (node (ref "R30") (pin "2") (pinfunction "2_2") (pintype "passive"))
      (node (ref "U$5") (pin "CELLS") (pinfunction "CELLS_CELLS") (pintype "bidirectional"))
      (node (ref "U$5") (pin "VREF33") (pinfunction "VREF33_VREF33") (pintype "bidirectional"))
    )
    (net (code "31") (name "Net-(D1--)") (class "Default")
      (node (ref "C12") (pin "1") (pinfunction "1_1") (pintype "passive"))
      (node (ref "D1") (pin "2") (pinfunction "-_2") (pintype "passive"))
      (node (ref "U$5") (pin "VIN") (pinfunction "VIN_VIN") (pintype "bidirectional"))
    )
    (net (code "32") (name "Net-(D2--)") (class "Default")
      (node (ref "C13") (pin "1") (pinfunction "1_1") (pintype "passive"))
      (node (ref "D2") (pin "2") (pinfunction "-_2") (pintype "passive"))
      (node (ref "L2") (pin "P$1") (pinfunction "P$1_P$1") (pintype "bidirectional"))
      (node (ref "U$5") (pin "SW") (pinfunction "SW_SW") (pintype "bidirectional"))
    )
    (net (code "33") (name "Net-(D3-PadA)") (class "Default")
      (node (ref "D3") (pin "A") (pinfunction "A_A") (pintype "passive"))
      (node (ref "R30") (pin "1") (pinfunction "1_1") (pintype "passive"))
    )
    (net (code "34") (name "Net-(D5-PadC)") (class "Default")
      (node (ref "D5") (pin "C") (pinfunction "C_C") (pintype "passive"))
      (node (ref "R31") (pin "1") (pinfunction "1_1") (pintype "passive"))
    )
    (net (code "35") (name "Net-(D6-PadA)") (class "Default")
      (node (ref "D6") (pin "A") (pinfunction "A_A") (pintype "passive"))
      (node (ref "R18") (pin "1") (pinfunction "1_1") (pintype "passive"))
    )
    (net (code "36") (name "Net-(L2-PadP$2)") (class "Default")
      (node (ref "L2") (pin "P$2") (pinfunction "P$2_P$2") (pintype "bidirectional"))
      (node (ref "R22") (pin "2") (pinfunction "2_2") (pintype "passive"))
      (node (ref "U$5") (pin "CSP") (pinfunction "CSP_CSP") (pintype "bidirectional"))
    )
    (net (code "37") (name "Net-(Q1-D)") (class "Default")
      (node (ref "Q1") (pin "3") (pinfunction "D_3") (pintype "passive"))
      (node (ref "U$7") (pin "NEG") (pinfunction "NEG_NEG") (pintype "bidirectional"))
    )
    (net (code "38") (name "Net-(Q2-D)") (class "Default")
      (node (ref "Q2") (pin "3") (pinfunction "D_3") (pintype "passive"))
      (node (ref "R8") (pin "2") (pinfunction "2_2") (pintype "passive"))
      (node (ref "R9") (pin "2") (pinfunction "2_2") (pintype "passive"))
    )
    (net (code "39") (name "Net-(Q3-D)") (class "Default")
      (node (ref "Q3") (pin "3") (pinfunction "D_3") (pintype "passive"))
      (node (ref "Q6") (pin "3") (pinfunction "G_3") (pintype "passive"))
      (node (ref "R34") (pin "1") (pinfunction "1_1") (pintype "passive"))
    )
    (net (code "40") (name "Net-(Q4-CATH)") (class "Default")
      (node (ref "Q4") (pin "CAT") (pinfunction "CATH_CAT") (pintype "bidirectional"))
      (node (ref "R8") (pin "1") (pinfunction "1_1") (pintype "passive"))
      (node (ref "TP16") (pin "1") (pinfunction "1_1") (pintype "passive"))
    )
    (net (code "41") (name "Net-(Q5-CATH)") (class "Default")
      (node (ref "Q5") (pin "CAT") (pinfunction "CATH_CAT") (pintype "bidirectional"))
      (node (ref "R9") (pin "1") (pinfunction "1_1") (pintype "passive"))
      (node (ref "TP17") (pin "1") (pinfunction "1_1") (pintype "passive"))
    )
    (net (code "42") (name "Net-(Q7-PadG)") (class "Default")
      (node (ref "Q7") (pin "G") (pinfunction "G_G") (pintype "bidirectional"))
      (node (ref "R23") (pin "1") (pinfunction "1_1") (pintype "passive"))
      (node (ref "R24") (pin "2") (pinfunction "2_2") (pintype "passive"))
      (node (ref "TP11") (pin "1") (pinfunction "1_1") (pintype "passive"))
    )
    (net (code "43") (name "Net-(R5-P$1)") (class "Default")
      (node (ref "JP4") (pin "1") (pinfunction "1_1") (pintype "passive"))
      (node (ref "R17") (pin "1") (pinfunction "1_1") (pintype "passive"))
      (node (ref "R5") (pin "P1") (pinfunction "P$1_P1") (pintype "bidirectional"))
      (node (ref "U$5") (pin "NTC") (pinfunction "NTC_NTC") (pintype "bidirectional"))
    )
    (net (code "44") (name "Net-(R20-Pad2)") (class "Default")
      (node (ref "R20") (pin "2") (pinfunction "2_2") (pintype "passive"))
      (node (ref "U$5") (pin "COMPV") (pinfunction "COMPV_COMPV") (pintype "bidirectional"))
    )
    (net (code "45") (name "Net-(R21-Pad2)") (class "Default")
      (node (ref "R21") (pin "2") (pinfunction "2_2") (pintype "passive"))
      (node (ref "U$5") (pin "COMPI") (pinfunction "COMPI_COMPI") (pintype "bidirectional"))
    )
    (net (code "46") (name "Net-(U$5-~{CHGOK})") (class "Default")
      (node (ref "D6") (pin "C") (pinfunction "C_C") (pintype "passive"))
      (node (ref "U$5") (pin "!CHGOK") (pinfunction "~{CHGOK}_!CHGOK") (pintype "bidirectional"))
    )
    (net (code "47") (name "Net-(U3-CAT)") (class "Default")
      (node (ref "R26") (pin "1") (pinfunction "1_1") (pintype "passive"))
      (node (ref "U3") (pin "CATH") (pinfunction "CAT_CATH") (pintype "bidirectional"))
    )
    (net (code "48") (name "Net-(U5-CAT)") (class "Default")
      (node (ref "R27") (pin "1") (pinfunction "1_1") (pintype "passive"))
      (node (ref "U5") (pin "CATH") (pinfunction "CAT_CATH") (pintype "bidirectional"))
    )
    (net (code "49") (name "Net-(U10-EN)") (class "Default")
      (node (ref "R1") (pin "1") (pinfunction "1_1") (pintype "passive"))
      (node (ref "TP29") (pin "1") (pinfunction "1_1") (pintype "passive"))
      (node (ref "U10") (pin "1") (pinfunction "PS/SYNC_1") (pintype "input"))
      (node (ref "U10") (pin "14") (pinfunction "EN_14") (pintype "input"))
    )
    (net (code "50") (name "Net-(U10-FB)") (class "Default")
      (node (ref "R2") (pin "1") (pinfunction "1_1") (pintype "passive"))
      (node (ref "R3") (pin "2") (pinfunction "2_2") (pintype "passive"))
      (node (ref "U10") (pin "5") (pinfunction "FB_5") (pintype "passive"))
    )
    (net (code "51") (name "Net-(U10-FB2)") (class "Default")
      (node (ref "TP27") (pin "1") (pinfunction "1_1") (pintype "passive"))
      (node (ref "U10") (pin "6") (pinfunction "FB2_6") (pintype "passive"))
    )
    (net (code "52") (name "Net-(U10-L1)") (class "Default")
      (node (ref "L1") (pin "P$1") (pinfunction "P$1_P$1") (pintype "bidirectional"))
      (node (ref "U10") (pin "11") (pinfunction "L1_11") (pintype "passive"))
    )
    (net (code "53") (name "Net-(U10-L2)") (class "Default")
      (node (ref "L1") (pin "P$2") (pinfunction "P$2_P$2") (pintype "bidirectional"))
      (node (ref "U10") (pin "9") (pinfunction "L2_9") (pintype "passive"))
    )
    (net (code "54") (name "Net-(U10-PG)") (class "Default")
      (node (ref "TP26") (pin "1") (pinfunction "1_1") (pintype "passive"))
      (node (ref "U10") (pin "2") (pinfunction "PG_2") (pintype "open_collector"))
    )
    (net (code "55") (name "Net-(U10-VAUX)") (class "Default")
      (node (ref "C7") (pin "1") (pinfunction "1_1") (pintype "passive"))
      (node (ref "U10") (pin "3") (pinfunction "VAUX_3") (pintype "output"))
    )
    (net (code "56") (name "Net-(U10-VSEL)") (class "Default")
      (node (ref "R4") (pin "2") (pinfunction "2_2") (pintype "passive"))
      (node (ref "TP28") (pin "1") (pinfunction "1_1") (pintype "passive"))
      (node (ref "U10") (pin "15") (pinfunction "VSEL_15") (pintype "input"))
    )
    (net (code "57") (name "OSC_IN") (class "Default")
      (node (ref "C3") (pin "1") (pinfunction "1_1") (pintype "passive"))
      (node (ref "U1") (pin "2") (pinfunction "PF0-OSC_IN_2") (pintype "bidirectional"))
      (node (ref "Y1") (pin "IN/OUT") (pinfunction "IN/OUT_IN/OUT") (pintype "passive"))
    )
    (net (code "58") (name "OSC_OUT") (class "Default")
      (node (ref "C4") (pin "1") (pinfunction "1_1") (pintype "passive"))
      (node (ref "U1") (pin "3") (pinfunction "PF1-OSC_OUT_3") (pintype "bidirectional"))
      (node (ref "Y1") (pin "OUT/IN") (pinfunction "OUT/IN_OUT/IN") (pintype "passive"))
    )
    (net (code "59") (name "PULSEOUT") (class "Default")
      (node (ref "J1") (pin "5") (pinfunction "5_5") (pintype "passive"))
      (node (ref "R13") (pin "1") (pinfunction "1_1") (pintype "passive"))
    )
    (net (code "60") (name "SENSOR1") (class "Default")
      (node (ref "Q4") (pin "E") (pinfunction "EMIT_E") (pintype "bidirectional"))
      (node (ref "R7") (pin "2") (pinfunction "2_2") (pintype "passive"))
      (node (ref "TP5") (pin "1") (pinfunction "1_1") (pintype "passive"))
      (node (ref "U1") (pin "28") (pinfunction "PB5_28") (pintype "bidirectional"))
    )
    (net (code "61") (name "SENSOR2") (class "Default")
      (node (ref "Q5") (pin "E") (pinfunction "EMIT_E") (pintype "bidirectional"))
      (node (ref "R10") (pin "2") (pinfunction "2_2") (pintype "passive"))
      (node (ref "TP7") (pin "1") (pinfunction "1_1") (pintype "passive"))
      (node (ref "U1") (pin "27") (pinfunction "PB4_27") (pintype "bidirectional"))
    )
    (net (code "62") (name "SENSOR_ON") (class "Default")
      (node (ref "Q2") (pin "1") (pinfunction "G_1") (pintype "passive"))
      (node (ref "R36") (pin "1") (pinfunction "1_1") (pintype "passive"))
      (node (ref "U1") (pin "26") (pinfunction "PB3_26") (pintype "bidirectional"))
    )
    (net (code "63") (name "SPKR") (class "Default")
      (node (ref "Q1") (pin "1") (pinfunction "G_1") (pintype "passive"))
      (node (ref "R37") (pin "1") (pinfunction "1_1") (pintype "passive"))
      (node (ref "U1") (pin "20") (pinfunction "PA10_20") (pintype "bidirectional"))
    )
    (net (code "64") (name "SWCLK") (class "Default")
      (node (ref "CM1") (pin "4") (pinfunction "SWDCLK/TCK_4") (pintype "passive"))
      (node (ref "U1") (pin "24") (pinfunction "PA14-SWCLK_24") (pintype "bidirectional"))
    )
    (net (code "65") (name "SWDIO") (class "Default")
      (node (ref "CM1") (pin "2") (pinfunction "SWDIO/TMS_2") (pintype "passive"))
      (node (ref "U1") (pin "23") (pinfunction "PA13-SWDIO_23") (pintype "bidirectional"))
    )
    (net (code "66") (name "T_GND") (class "Default")
      (node (ref "JP2") (pin "7") (pinfunction "7_7") (pintype "passive"))
      (node (ref "R26") (pin "2") (pinfunction "2_2") (pintype "passive"))
      (node (ref "R27") (pin "2") (pinfunction "2_2") (pintype "passive"))
    )
    (net (code "67") (name "USART2_RX") (class "Default")
      (node (ref "JP3") (pin "1") (pinfunction "1_1") (pintype "passive"))
      (node (ref "TP3") (pin "1") (pinfunction "1_1") (pintype "passive"))
      (node (ref "U1") (pin "25") (pinfunction "PA15_25") (pintype "bidirectional"))
    )
    (net (code "68") (name "USART2_TX") (class "Default")
      (node (ref "JP3") (pin "2") (pinfunction "2_2") (pintype "passive"))
      (node (ref "TP4") (pin "1") (pinfunction "1_1") (pintype "passive"))
      (node (ref "U1") (pin "8") (pinfunction "PA2_8") (pintype "bidirectional"))
    )
    (net (code "69") (name "VBAT") (class "Default")
      (node (ref "C17") (pin "1") (pinfunction "1_1") (pintype "passive"))
      (node (ref "JP1") (pin "1") (pinfunction "1_1") (pintype "passive"))
      (node (ref "JP1") (pin "2") (pinfunction "2_2") (pintype "passive"))
      (node (ref "Q7") (pin "S1") (pinfunction "S_S1") (pintype "bidirectional"))
      (node (ref "Q7") (pin "S2") (pinfunction "S_S2") (pintype "bidirectional"))
      (node (ref "Q7") (pin "S3") (pinfunction "S_S3") (pintype "bidirectional"))
      (node (ref "R15") (pin "2") (pinfunction "2_2") (pintype "passive"))
      (node (ref "R22") (pin "1") (pinfunction "1_1") (pintype "passive"))
      (node (ref "R25") (pin "2") (pinfunction "2_2") (pintype "passive"))
      (node (ref "U$5") (pin "BATT") (pinfunction "BATT_BATT") (pintype "bidirectional"))
    )
    (net (code "70") (name "VUMB") (class "Default")
      (node (ref "C11") (pin "1") (pinfunction "1_1") (pintype "passive"))
      (node (ref "D1") (pin "1") (pinfunction "+_1") (pintype "passive"))
      (node (ref "JP2") (pin "3") (pinfunction "3_3") (pintype "passive"))
      (node (ref "U$5") (pin "VCC") (pinfunction "VCC_VCC") (pintype "bidirectional"))
    )
    (net (code "71") (name "unconnected-(CM1-NC{slash}TDI-Pad8)") (class "Default")
      (node (ref "CM1") (pin "8") (pinfunction "NC/TDI_8") (pintype "passive"))
    )
    (net (code "72") (name "unconnected-(CM1-SWO{slash}TDO-Pad6)") (class "Default")
      (node (ref "CM1") (pin "6") (pinfunction "SWO/TDO_6") (pintype "passive"))
    )
    (net (code "73") (name "unconnected-(U1-PB6-Pad29)") (class "Default")
      (node (ref "U1") (pin "29") (pinfunction "PB6_29") (pintype "bidirectional"))
    )
    (net (code "74") (name "unconnected-(U1-PB8-BOOT0-Pad31)") (class "Default")
      (node (ref "U1") (pin "31") (pinfunction "PB8-BOOT0_31") (pintype "bidirectional"))
    )
  )
)
